# led_driver_AL8805.net
KiCad netlist of a schematic drawn in EAGLE
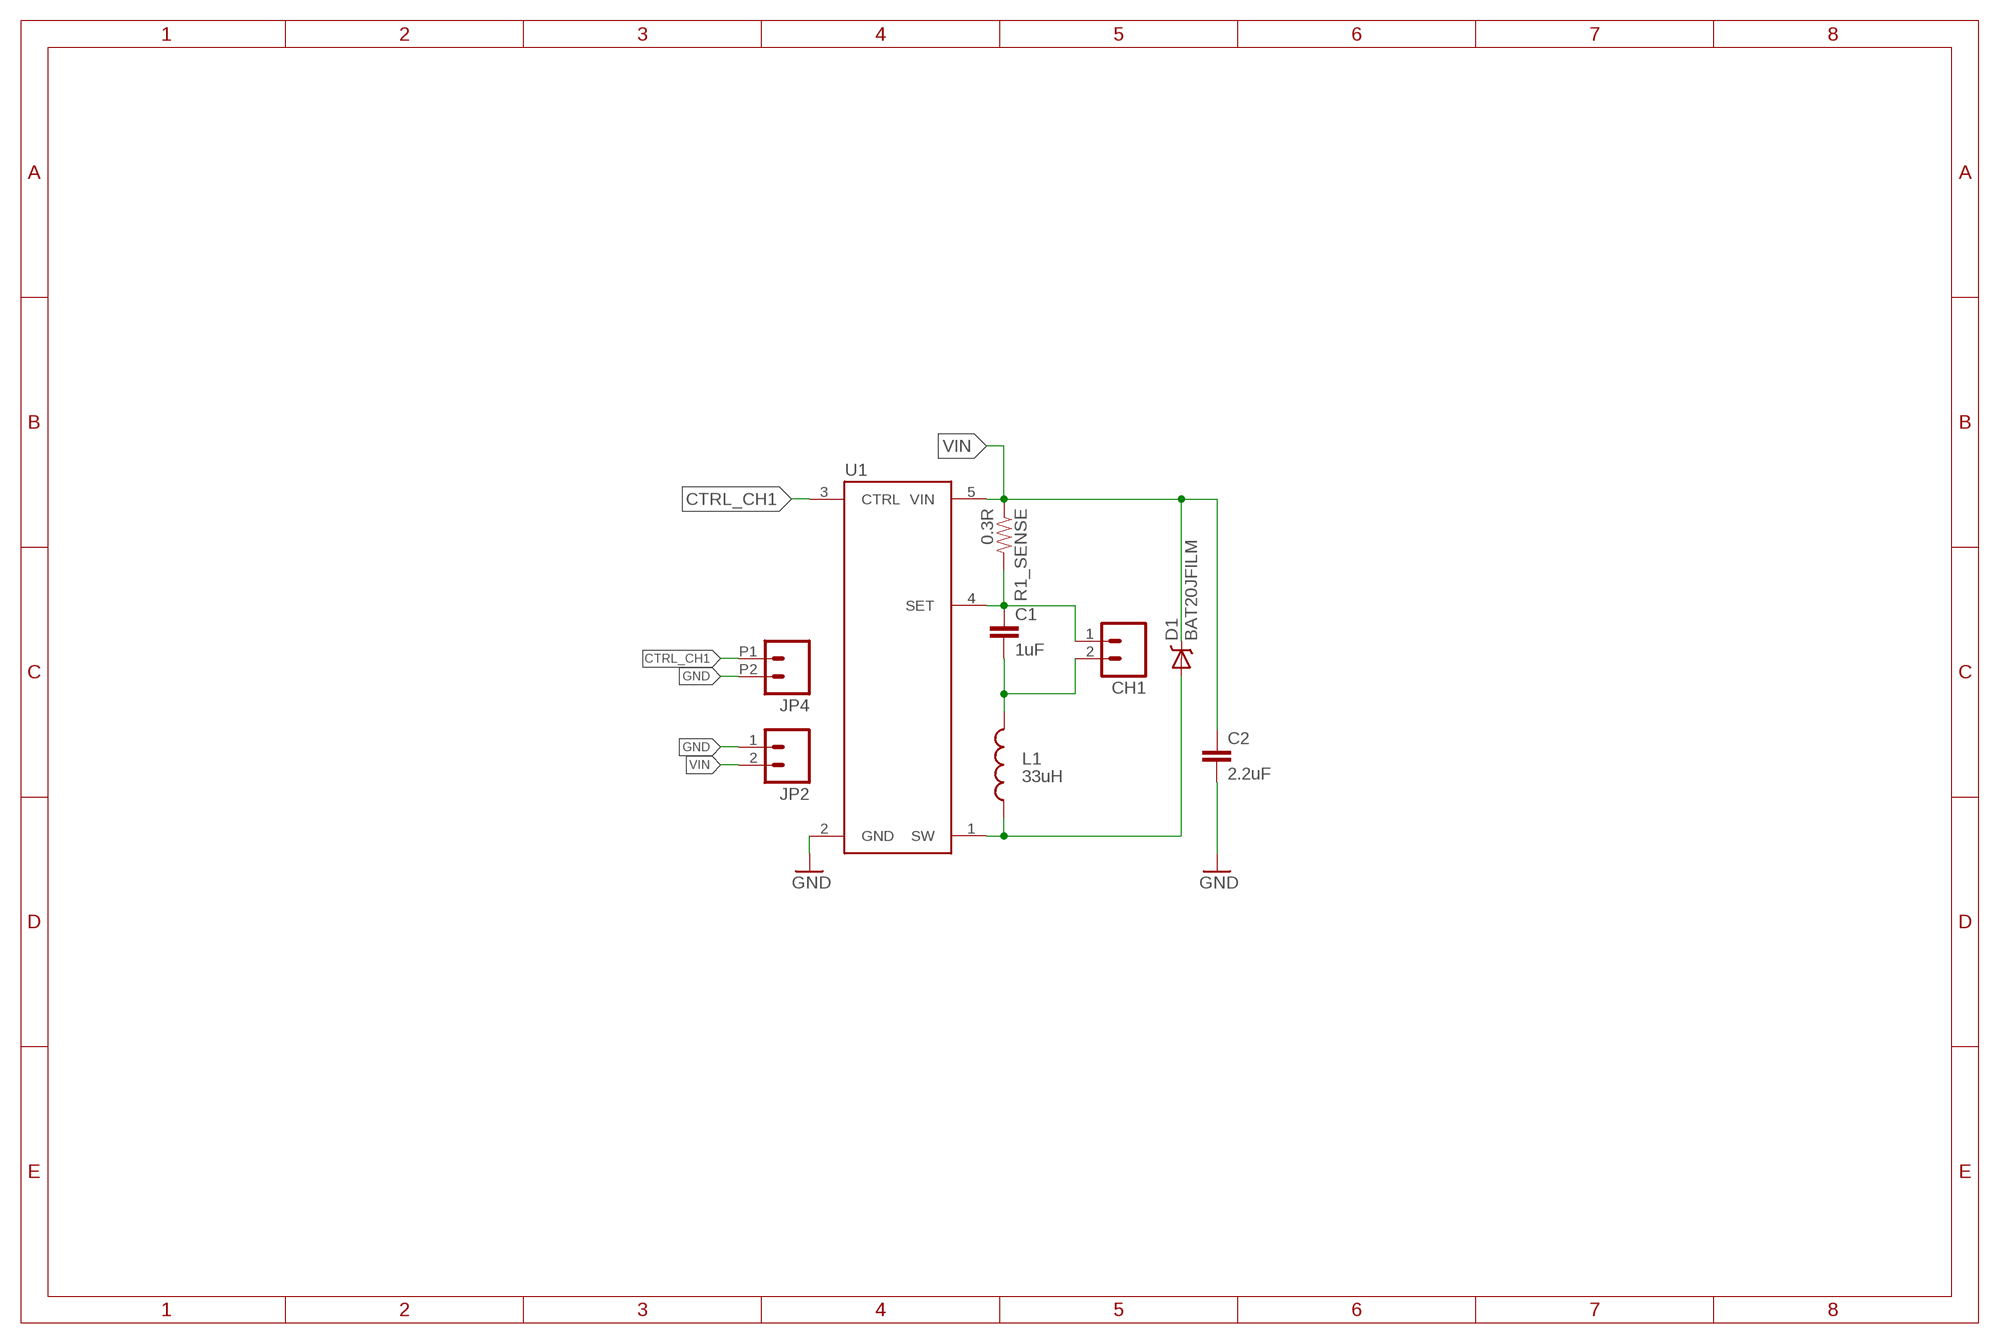
[diagram p0: schematic, sheet 1]

(export (version "E")
  (design (tool "Eeschema 10.0.6"))
  (components
    (comp (ref "C1")
      (value "1uF")
      (footprint "eagle-import:0805")
      (libsource (lib "eagle-import") (part "1.0UF-25V-+80/-20(0805)"))
    )
    (comp (ref "C2")
      (value "2.2uF")
      (footprint "eagle-import:0805")
      (libsource (lib "eagle-import") (part "2.2UF-25V-+80/-20(0805)"))
    )
    (comp (ref "CH1")
      (value "M023.5MM_LOCK")
      (footprint "eagle-import:SCREWTERMINAL-3.5MM-2_LOCK")
      (libsource (lib "eagle-import") (part "M023.5MM_LOCK"))
    )
    (comp (ref "D1")
      (value "BAT20JFILM")
      (footprint "eagle-import:SOD-323")
      (libsource (lib "eagle-import") (part "BAT20JFILM"))
    )
    (comp (ref "JP2")
      (value "M023.5MM_LOCK")
      (footprint "eagle-import:SCREWTERMINAL-3.5MM-2_LOCK")
      (libsource (lib "eagle-import") (part "M023.5MM_LOCK"))
    )
    (comp (ref "JP4")
      (value "M022.54MM_SCREWTERM")
      (footprint "eagle-import:1X02_2.54_SCREWTERM")
      (libsource (lib "eagle-import") (part "M022.54MM_SCREWTERM"))
    )
    (comp (ref "L1")
      (value "33uH")
      (footprint "eagle-import:SRN6045")
      (libsource (lib "eagle-import") (part "INDUCTORBOURNS_SRN6045"))
    )
    (comp (ref "R1_SENSE")
      (value "0.3R")
      (footprint "eagle-import:0805")
      (libsource (lib "eagle-import") (part "0.3OHM-1/8W-1%(0805)"))
    )
    (comp (ref "U1")
      (value "AL8805")
      (footprint "eagle-import:SOT23-5")
      (libsource (lib "eagle-import") (part "AL8805"))
    )
  )
  (nets
    (net (code "1") (name "CTRL_CH1") (class "Default")
      (node (ref "JP4") (pin "P1") (pinfunction "1_P1") (pintype "passive"))
      (node (ref "U1") (pin "3") (pinfunction "CTRL_3") (pintype "bidirectional"))
    )
    (net (code "2") (name "GND") (class "Default")
      (node (ref "C2") (pin "2") (pinfunction "2_2") (pintype "passive"))
      (node (ref "JP2") (pin "1") (pinfunction "1_1") (pintype "passive"))
      (node (ref "JP4") (pin "P2") (pinfunction "2_P2") (pintype "passive"))
      (node (ref "U1") (pin "2") (pinfunction "GND_2") (pintype "bidirectional"))
    )
    (net (code "3") (name "Net-(C1-Pad2)") (class "Default")
      (node (ref "C1") (pin "2") (pinfunction "2_2") (pintype "passive"))
      (node (ref "CH1") (pin "2") (pinfunction "2_2") (pintype "passive"))
      (node (ref "L1") (pin "2") (pinfunction "2_2") (pintype "passive"))
    )
    (net (code "4") (name "Net-(D1-A)") (class "Default")
      (node (ref "D1") (pin "2") (pinfunction "A_2") (pintype "passive"))
      (node (ref "L1") (pin "1") (pinfunction "1_1") (pintype "passive"))
      (node (ref "U1") (pin "1") (pinfunction "SW_1") (pintype "bidirectional"))
    )
    (net (code "5") (name "Net-(U1-SET)") (class "Default")
      (node (ref "C1") (pin "1") (pinfunction "1_1") (pintype "passive"))
      (node (ref "CH1") (pin "1") (pinfunction "1_1") (pintype "passive"))
      (node (ref "R1_SENSE") (pin "2") (pinfunction "2_2") (pintype "passive"))
      (node (ref "U1") (pin "4") (pinfunction "SET_4") (pintype "bidirectional"))
    )
    (net (code "6") (name "VIN") (class "Default")
      (node (ref "C2") (pin "1") (pinfunction "1_1") (pintype "passive"))
      (node (ref "D1") (pin "1") (pinfunction "C_1") (pintype "passive"))
      (node (ref "JP2") (pin "2") (pinfunction "2_2") (pintype "passive"))
      (node (ref "R1_SENSE") (pin "1") (pinfunction "1_1") (pintype "passive"))
      (node (ref "U1") (pin "5") (pinfunction "VIN_5") (pintype "bidirectional"))
    )
  )
)
